# test_node.net
KiCad netlist of a schematic drawn in EasyEDA
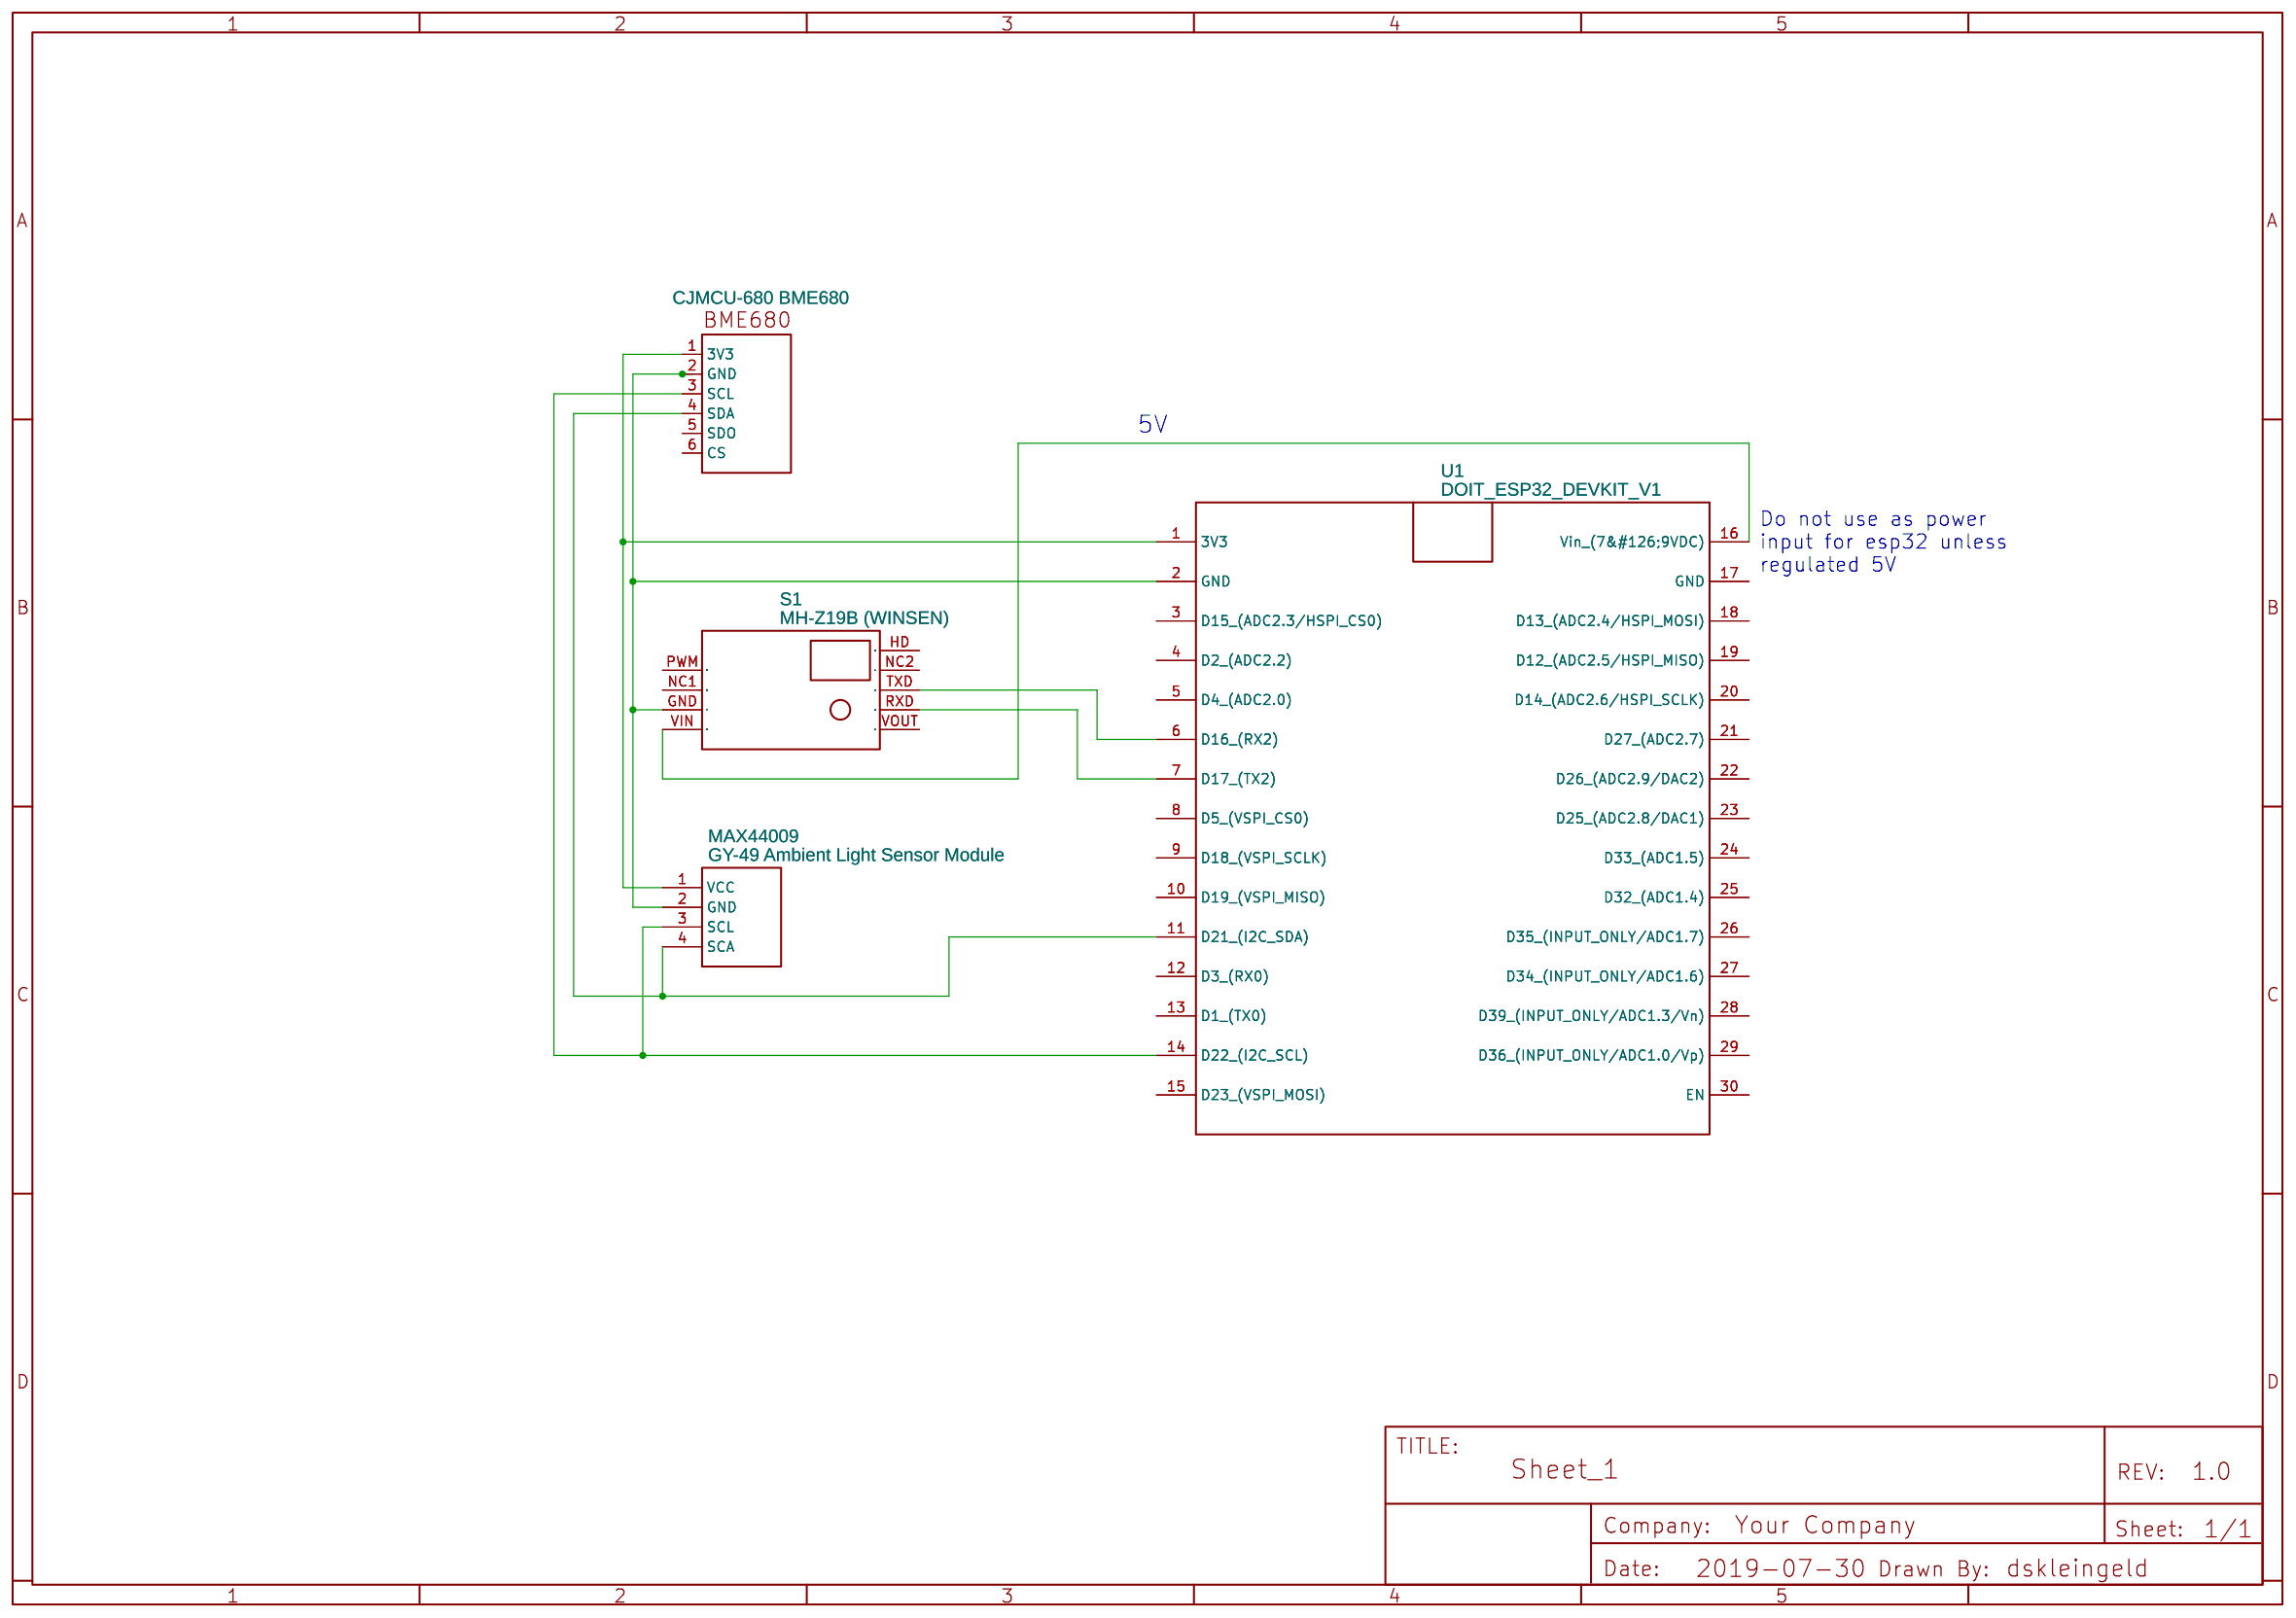
[diagram p0: schematic sheet]

(export (version "E")
  (design (tool "Eeschema 10.0.6"))
  (components
    (comp (ref "MAX44009")
      (value "GY-49 Ambient Light Sensor Module")
      (fields (field (name "BOM_Manufacturer Part") "?"))
      (libsource (lib "") (part "Unknown_220_400"))
    )
    (comp (ref "S1")
      (value "MH-Z19B (WINSEN)")
      (fields (field (name "BOM_Manufacturer Part") "MH-Z19 (WINSEN)"))
      (libsource (lib "") (part "Unknown_200_310"))
    )
    (comp (ref "U1")
      (value "DOIT_ESP32_DEVKIT_V1")
      (fields (field (name "BOM_Manufacturer Part") "DOIT ESP32 DEVKIT V1"))
      (libsource (lib "") (part "Unknown_430_205"))
    )
    (comp (ref "U2")
      (value "CJMCU-680 BME680")
      (fields (field (name "BOM_Manufacturer Part") "BME680") (field (name "BOM_Supplier Part") "C125972"))
      (libsource (lib "") (part "Unknown_215_140"))
    )
  )
  (nets
    (net (code "1") (name "Net-(MAX44009-GND)") (class "Default")
      (node (ref "MAX44009") (pin "2") (pinfunction "GND_2") (pintype "unspecified"))
      (node (ref "S1") (pin "GND") (pinfunction "7_GND") (pintype "unspecified"))
      (node (ref "U1") (pin "2") (pinfunction "GND_2") (pintype "unspecified"))
      (node (ref "U2") (pin "2") (pinfunction "GND_2") (pintype "unspecified"))
    )
    (net (code "2") (name "Net-(MAX44009-SCA)") (class "Default")
      (node (ref "MAX44009") (pin "4") (pinfunction "SCA_4") (pintype "unspecified"))
      (node (ref "U1") (pin "11") (pinfunction "D21_(I2C_SDA)_11") (pintype "unspecified"))
      (node (ref "U2") (pin "4") (pinfunction "SDA_4") (pintype "unspecified"))
    )
    (net (code "3") (name "Net-(MAX44009-SCL)") (class "Default")
      (node (ref "MAX44009") (pin "3") (pinfunction "SCL_3") (pintype "unspecified"))
      (node (ref "U1") (pin "14") (pinfunction "D22_(I2C_SCL)_14") (pintype "unspecified"))
      (node (ref "U2") (pin "3") (pinfunction "SCL_3") (pintype "unspecified"))
    )
    (net (code "4") (name "Net-(MAX44009-VCC)") (class "Default")
      (node (ref "MAX44009") (pin "1") (pinfunction "VCC_1") (pintype "unspecified"))
      (node (ref "U1") (pin "1") (pinfunction "3V3_1") (pintype "unspecified"))
      (node (ref "U2") (pin "1") (pinfunction "3V3_1") (pintype "unspecified"))
    )
    (net (code "5") (name "Net-(S1-2)") (class "Default")
      (node (ref "S1") (pin "RXD") (pinfunction "2_RXD") (pintype "unspecified"))
      (node (ref "U1") (pin "7") (pinfunction "D17_(TX2)_7") (pintype "unspecified"))
    )
    (net (code "6") (name "Net-(S1-3)") (class "Default")
      (node (ref "S1") (pin "TXD") (pinfunction "3_TXD") (pintype "unspecified"))
      (node (ref "U1") (pin "6") (pinfunction "D16_(RX2)_6") (pintype "unspecified"))
    )
    (net (code "7") (name "Net-(S1-6)") (class "Default")
      (node (ref "S1") (pin "VIN") (pinfunction "6_VIN") (pintype "unspecified"))
      (node (ref "U1") (pin "16") (pinfunction "Vin_(7&#126;9VDC)_16") (pintype "unspecified"))
    )
    (net (code "8") (name "unconnected-(S1-1-PadVOUT)") (class "Default")
      (node (ref "S1") (pin "VOUT") (pinfunction "1_VOUT") (pintype "unspecified"))
    )
    (net (code "9") (name "unconnected-(S1-4-PadNC2)") (class "Default")
      (node (ref "S1") (pin "NC2") (pinfunction "4_NC2") (pintype "unspecified"))
    )
    (net (code "10") (name "unconnected-(S1-5-PadHD)") (class "Default")
      (node (ref "S1") (pin "HD") (pinfunction "5_HD") (pintype "unspecified"))
    )
    (net (code "11") (name "unconnected-(S1-8-PadNC1)") (class "Default")
      (node (ref "S1") (pin "NC1") (pinfunction "8_NC1") (pintype "unspecified"))
    )
    (net (code "12") (name "unconnected-(S1-9-PadPWM)") (class "Default")
      (node (ref "S1") (pin "PWM") (pinfunction "9_PWM") (pintype "unspecified"))
    )
    (net (code "13") (name "unconnected-(U1-D1_(TX0)-Pad13)") (class "Default")
      (node (ref "U1") (pin "13") (pinfunction "D1_(TX0)_13") (pintype "unspecified"))
    )
    (net (code "14") (name "unconnected-(U1-D2_(ADC2.2)-Pad4)") (class "Default")
      (node (ref "U1") (pin "4") (pinfunction "D2_(ADC2.2)_4") (pintype "unspecified"))
    )
    (net (code "15") (name "unconnected-(U1-D3_(RX0)-Pad12)") (class "Default")
      (node (ref "U1") (pin "12") (pinfunction "D3_(RX0)_12") (pintype "unspecified"))
    )
    (net (code "16") (name "unconnected-(U1-D4_(ADC2.0)-Pad5)") (class "Default")
      (node (ref "U1") (pin "5") (pinfunction "D4_(ADC2.0)_5") (pintype "unspecified"))
    )
    (net (code "17") (name "unconnected-(U1-D5_(VSPI_CS0)-Pad8)") (class "Default")
      (node (ref "U1") (pin "8") (pinfunction "D5_(VSPI_CS0)_8") (pintype "unspecified"))
    )
    (net (code "18") (name "unconnected-(U1-D12_(ADC2.5{slash}HSPI_MISO)-Pad19)") (class "Default")
      (node (ref "U1") (pin "19") (pinfunction "D12_(ADC2.5/HSPI_MISO)_19") (pintype "unspecified"))
    )
    (net (code "19") (name "unconnected-(U1-D13_(ADC2.4{slash}HSPI_MOSI)-Pad18)") (class "Default")
      (node (ref "U1") (pin "18") (pinfunction "D13_(ADC2.4/HSPI_MOSI)_18") (pintype "unspecified"))
    )
    (net (code "20") (name "unconnected-(U1-D14_(ADC2.6{slash}HSPI_SCLK)-Pad20)") (class "Default")
      (node (ref "U1") (pin "20") (pinfunction "D14_(ADC2.6/HSPI_SCLK)_20") (pintype "unspecified"))
    )
    (net (code "21") (name "unconnected-(U1-D15_(ADC2.3{slash}HSPI_CS0)-Pad3)") (class "Default")
      (node (ref "U1") (pin "3") (pinfunction "D15_(ADC2.3/HSPI_CS0)_3") (pintype "unspecified"))
    )
    (net (code "22") (name "unconnected-(U1-D18_(VSPI_SCLK)-Pad9)") (class "Default")
      (node (ref "U1") (pin "9") (pinfunction "D18_(VSPI_SCLK)_9") (pintype "unspecified"))
    )
    (net (code "23") (name "unconnected-(U1-D19_(VSPI_MISO)-Pad10)") (class "Default")
      (node (ref "U1") (pin "10") (pinfunction "D19_(VSPI_MISO)_10") (pintype "unspecified"))
    )
    (net (code "24") (name "unconnected-(U1-D23_(VSPI_MOSI)-Pad15)") (class "Default")
      (node (ref "U1") (pin "15") (pinfunction "D23_(VSPI_MOSI)_15") (pintype "unspecified"))
    )
    (net (code "25") (name "unconnected-(U1-D25_(ADC2.8{slash}DAC1)-Pad23)") (class "Default")
      (node (ref "U1") (pin "23") (pinfunction "D25_(ADC2.8/DAC1)_23") (pintype "unspecified"))
    )
    (net (code "26") (name "unconnected-(U1-D26_(ADC2.9{slash}DAC2)-Pad22)") (class "Default")
      (node (ref "U1") (pin "22") (pinfunction "D26_(ADC2.9/DAC2)_22") (pintype "unspecified"))
    )
    (net (code "27") (name "unconnected-(U1-D27_(ADC2.7)-Pad21)") (class "Default")
      (node (ref "U1") (pin "21") (pinfunction "D27_(ADC2.7)_21") (pintype "unspecified"))
    )
    (net (code "28") (name "unconnected-(U1-D32_(ADC1.4)-Pad25)") (class "Default")
      (node (ref "U1") (pin "25") (pinfunction "D32_(ADC1.4)_25") (pintype "unspecified"))
    )
    (net (code "29") (name "unconnected-(U1-D33_(ADC1.5)-Pad24)") (class "Default")
      (node (ref "U1") (pin "24") (pinfunction "D33_(ADC1.5)_24") (pintype "unspecified"))
    )
    (net (code "30") (name "unconnected-(U1-D34_(INPUT_ONLY{slash}ADC1.6)-Pad27)") (class "Default")
      (node (ref "U1") (pin "27") (pinfunction "D34_(INPUT_ONLY/ADC1.6)_27") (pintype "unspecified"))
    )
    (net (code "31") (name "unconnected-(U1-D35_(INPUT_ONLY{slash}ADC1.7)-Pad26)") (class "Default")
      (node (ref "U1") (pin "26") (pinfunction "D35_(INPUT_ONLY/ADC1.7)_26") (pintype "unspecified"))
    )
    (net (code "32") (name "unconnected-(U1-D36_(INPUT_ONLY{slash}ADC1.0{slash}Vp)-Pad29)") (class "Default")
      (node (ref "U1") (pin "29") (pinfunction "D36_(INPUT_ONLY/ADC1.0/Vp)_29") (pintype "unspecified"))
    )
    (net (code "33") (name "unconnected-(U1-D39_(INPUT_ONLY{slash}ADC1.3{slash}Vn)-Pad28)") (class "Default")
      (node (ref "U1") (pin "28") (pinfunction "D39_(INPUT_ONLY/ADC1.3/Vn)_28") (pintype "unspecified"))
    )
    (net (code "34") (name "unconnected-(U1-EN-Pad30)") (class "Default")
      (node (ref "U1") (pin "30") (pinfunction "EN_30") (pintype "unspecified"))
    )
    (net (code "35") (name "unconnected-(U1-GND-Pad17)") (class "Default")
      (node (ref "U1") (pin "17") (pinfunction "GND_17") (pintype "unspecified"))
    )
    (net (code "36") (name "unconnected-(U2-CS-Pad6)") (class "Default")
      (node (ref "U2") (pin "6") (pinfunction "CS_6") (pintype "unspecified"))
    )
    (net (code "37") (name "unconnected-(U2-SDO-Pad5)") (class "Default")
      (node (ref "U2") (pin "5") (pinfunction "SDO_5") (pintype "unspecified"))
    )
  )
)
